# SHT30.net
KiCad netlist of a schematic drawn in Altium Designer
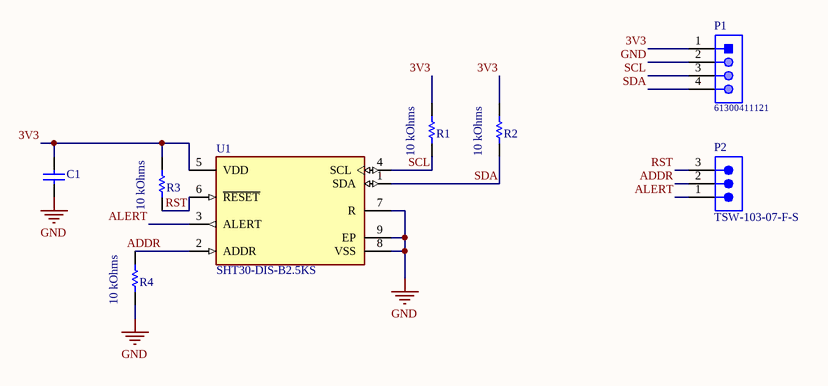
[diagram p0: SHT30.SchDoc]

(export (version "E")
  (design (tool "Eeschema 10.0.6"))
  (components
    (comp (ref "C1")
      (value "C0805C106K4PACTU")
      (footprint "CAPC2013X140X50ML20T25")
      (description "10µF ±10% 16V Ceramic Capacitor X5R 0805 (2012 Metric)")
      (fields (field (name "PART NUMBER") "CL21A106KOQNNNG"))
      (libsource (lib "Altium Content Vault") (part "CAP"))
    )
    (comp (ref "P1")
      (value "61300411121")
      (footprint "61300411121")
      (description "THT Vertical Pin Header WR-PHD, Pitch 2.54 mm, Single Row, 4 pins")
      (fields (field (name "MANUFACTURER") "Wurth Elektronik") (field (name "PUBLISHER") "WurthElektronik"))
      (libsource (lib "Altium Content Vault") (part "WE-CN-1P-M-R4"))
    )
    (comp (ref "P2")
      (value "TSW-103-07-F-S")
      (footprint "SMTC-TSW-103-07-X-S")
      (description "0.025\" SQ Post Header, Through-hole, Vertical, -55 to 125 degC, 2.54 mm Pitch, 3-Pin, Male, RoHS")
      (fields (field (name "MANUFACTURER") "Samtec"))
      (libsource (lib "Altium Content Vault") (part "SMTC-TSW-103-X-X-S-X"))
    )
    (comp (ref "R1")
      (value "10 kOhms")
      (footprint "RESC2013X60X30ML20T20")
      (fields (field (name "PART NUMBER") "RK73B2ATTD103J") (field (name "MANUFACTURER") "KOA Speer"))
      (libsource (lib "Altium Content Vault") (part "RES"))
    )
    (comp (ref "R2")
      (value "10 kOhms")
      (footprint "RESC2013X60X30ML20T20")
      (fields (field (name "PART NUMBER") "RK73B2ATTD103J") (field (name "MANUFACTURER") "KOA Speer"))
      (libsource (lib "Altium Content Vault") (part "RES"))
    )
    (comp (ref "R3")
      (value "10 kOhms")
      (footprint "RESC2013X60X30ML20T20")
      (fields (field (name "PART NUMBER") "RK73B2ATTD103J") (field (name "MANUFACTURER") "KOA Speer"))
      (libsource (lib "Altium Content Vault") (part "RES"))
    )
    (comp (ref "R4")
      (value "10 kOhms")
      (footprint "RESC2013X60X30ML20T20")
      (fields (field (name "PART NUMBER") "RK73B2ATTD103J") (field (name "MANUFACTURER") "KOA Speer"))
      (libsource (lib "Altium Content Vault") (part "RES"))
    )
    (comp (ref "U1")
      (value "SHT30-DIS-B2.5KS")
      (footprint "FP-SHT30-DIS-B2_5KS-IPC_A")
      (description "SENSOR HUMID/TEMP 5V I2C 3% SMD")
      (libsource (lib "Altium Content Vault") (part "3a40f6fddac460f1c5fb2adec20f0f2"))
    )
  )
  (nets
    (net (code "1") (name "/3V3") (class "Default")
      (node (ref "C1") (pin "2") (pinfunction "2_2") (pintype "passive"))
      (node (ref "P1") (pin "1") (pinfunction "1_1") (pintype "passive"))
      (node (ref "R1") (pin "1") (pinfunction "1_1") (pintype "passive"))
      (node (ref "R2") (pin "1") (pinfunction "1_1") (pintype "passive"))
      (node (ref "R3") (pin "1") (pinfunction "1_1") (pintype "passive"))
      (node (ref "U1") (pin "5") (pinfunction "VDD_5") (pintype "power_in"))
    )
    (net (code "2") (name "/ADDR") (class "Default")
      (node (ref "P2") (pin "2") (pinfunction "2_2") (pintype "passive"))
      (node (ref "R4") (pin "1") (pinfunction "1_1") (pintype "passive"))
      (node (ref "U1") (pin "2") (pinfunction "ADDR_2") (pintype "input"))
    )
    (net (code "3") (name "/ALERT") (class "Default")
      (node (ref "P2") (pin "1") (pinfunction "1_1") (pintype "passive"))
      (node (ref "U1") (pin "3") (pinfunction "ALERT_3") (pintype "output"))
    )
    (net (code "4") (name "/RST") (class "Default")
      (node (ref "P2") (pin "3") (pinfunction "3_3") (pintype "passive"))
      (node (ref "R3") (pin "2") (pinfunction "2_2") (pintype "passive"))
      (node (ref "U1") (pin "6") (pinfunction "~{RESET}_6") (pintype "input"))
    )
    (net (code "5") (name "/SCL") (class "Default")
      (node (ref "P1") (pin "3") (pinfunction "3_3") (pintype "passive"))
      (node (ref "R1") (pin "2") (pinfunction "2_2") (pintype "passive"))
      (node (ref "U1") (pin "4") (pinfunction "SCL_4") (pintype "bidirectional"))
    )
    (net (code "6") (name "/SDA") (class "Default")
      (node (ref "P1") (pin "4") (pinfunction "4_4") (pintype "passive"))
      (node (ref "R2") (pin "2") (pinfunction "2_2") (pintype "passive"))
      (node (ref "U1") (pin "1") (pinfunction "SDA_1") (pintype "bidirectional"))
    )
    (net (code "7") (name "GND") (class "Default")
      (node (ref "C1") (pin "1") (pinfunction "1_1") (pintype "passive"))
      (node (ref "P1") (pin "2") (pinfunction "2_2") (pintype "passive"))
      (node (ref "R4") (pin "2") (pinfunction "2_2") (pintype "passive"))
      (node (ref "U1") (pin "7") (pinfunction "R_7") (pintype "passive"))
      (node (ref "U1") (pin "8") (pinfunction "VSS_8") (pintype "power_in"))
      (node (ref "U1") (pin "9") (pinfunction "EP_9") (pintype "passive"))
    )
  )
)
